# H-bridge.net
KiCad netlist of a schematic drawn in EAGLE
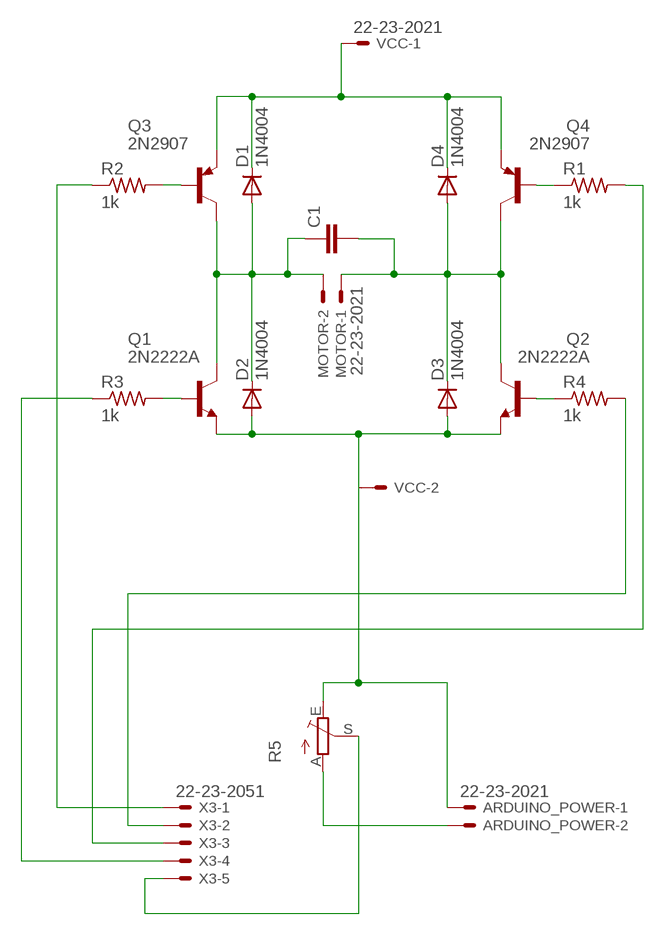
[diagram p0: schematic, sheet 1]

(export (version "E")
  (design (tool "Eeschema 10.0.6"))
  (components
    (comp (ref "ARDUINO_POWER")
      (value "22-23-2021")
      (footprint "eagle-import:22-23-2021")
      (fields (field (name "MF") "MOLEX"))
      (libsource (lib "eagle-import") (part "22-23-2021"))
    )
    (comp (ref "C1")
      (value "C2.5/2")
      (footprint "eagle-import:C2.5-2")
      (libsource (lib "eagle-import") (part "C2.5/2"))
    )
    (comp (ref "D1")
      (value "1N4004")
      (footprint "eagle-import:DO41-10")
      (libsource (lib "eagle-import") (part "1N4004"))
    )
    (comp (ref "D2")
      (value "1N4004")
      (footprint "eagle-import:DO41-10")
      (libsource (lib "eagle-import") (part "1N4004"))
    )
    (comp (ref "D3")
      (value "1N4004")
      (footprint "eagle-import:DO41-10")
      (libsource (lib "eagle-import") (part "1N4004"))
    )
    (comp (ref "D4")
      (value "1N4004")
      (footprint "eagle-import:DO41-10")
      (libsource (lib "eagle-import") (part "1N4004"))
    )
    (comp (ref "MOTOR")
      (value "22-23-2021")
      (footprint "eagle-import:22-23-2021")
      (fields (field (name "MF") "MOLEX"))
      (libsource (lib "eagle-import") (part "22-23-2021"))
    )
    (comp (ref "Q1")
      (value "2N2222A")
      (footprint "eagle-import:TO18")
      (libsource (lib "eagle-import") (part "2N2222A"))
    )
    (comp (ref "Q2")
      (value "2N2222A")
      (footprint "eagle-import:TO18")
      (libsource (lib "eagle-import") (part "2N2222A"))
    )
    (comp (ref "Q3")
      (value "2N2907")
      (footprint "eagle-import:TO18")
      (libsource (lib "eagle-import") (part "2N2907"))
    )
    (comp (ref "Q4")
      (value "2N2907")
      (footprint "eagle-import:TO18")
      (libsource (lib "eagle-import") (part "2N2907"))
    )
    (comp (ref "R1")
      (value "1k")
      (footprint "eagle-import:0309_12")
      (libsource (lib "eagle-import") (part "R-US_0309/12"))
    )
    (comp (ref "R2")
      (value "1k")
      (footprint "eagle-import:0309_12")
      (libsource (lib "eagle-import") (part "R-US_0309/12"))
    )
    (comp (ref "R3")
      (value "1k")
      (footprint "eagle-import:0309_12")
      (libsource (lib "eagle-import") (part "R-US_0309/12"))
    )
    (comp (ref "R4")
      (value "1k")
      (footprint "eagle-import:0309_12")
      (libsource (lib "eagle-import") (part "R-US_0309/12"))
    )
    (comp (ref "R5")
      (value "TRIM_EU-CA6V")
      (footprint "eagle-import:CA6V")
      (libsource (lib "eagle-import") (part "TRIM_EU-CA6V"))
    )
    (comp (ref "VCC")
      (value "22-23-2021")
      (footprint "eagle-import:22-23-2021")
      (fields (field (name "MF") "MOLEX"))
      (libsource (lib "eagle-import") (part "22-23-2021"))
    )
    (comp (ref "X3")
      (value "22-23-2051")
      (footprint "eagle-import:22-23-2051")
      (fields (field (name "MF") "MOLEX"))
      (libsource (lib "eagle-import") (part "22-23-2051"))
    )
  )
  (nets
    (net (code "1") (name "Net-(ARDUINO_POWERA-S)") (class "Default")
      (node (ref "ARDUINO_POWER") (pin "1") (pinfunction "S_1") (pintype "passive"))
      (node (ref "D2") (pin "A") (pinfunction "A_A") (pintype "passive"))
      (node (ref "D3") (pin "A") (pinfunction "A_A") (pintype "passive"))
      (node (ref "Q1") (pin "1") (pinfunction "E_1") (pintype "passive"))
      (node (ref "Q2") (pin "1") (pinfunction "E_1") (pintype "passive"))
      (node (ref "R5") (pin "E") (pinfunction "E_E") (pintype "passive"))
      (node (ref "VCC") (pin "2") (pinfunction "S_2") (pintype "passive"))
    )
    (net (code "2") (name "Net-(ARDUINO_POWERB-S)") (class "Default")
      (node (ref "ARDUINO_POWER") (pin "2") (pinfunction "S_2") (pintype "passive"))
      (node (ref "R5") (pin "A") (pinfunction "A_A") (pintype "passive"))
    )
    (net (code "3") (name "Net-(MOTORA-S)") (class "Default")
      (node (ref "C1") (pin "2") (pinfunction "2_2") (pintype "passive"))
      (node (ref "D3") (pin "C") (pinfunction "C_C") (pintype "passive"))
      (node (ref "D4") (pin "A") (pinfunction "A_A") (pintype "passive"))
      (node (ref "MOTOR") (pin "1") (pinfunction "S_1") (pintype "passive"))
      (node (ref "Q2") (pin "3") (pinfunction "C_3") (pintype "passive"))
      (node (ref "Q4") (pin "3") (pinfunction "C_3") (pintype "passive"))
    )
    (net (code "4") (name "Net-(MOTORB-S)") (class "Default")
      (node (ref "C1") (pin "1") (pinfunction "1_1") (pintype "passive"))
      (node (ref "D1") (pin "A") (pinfunction "A_A") (pintype "passive"))
      (node (ref "D2") (pin "C") (pinfunction "C_C") (pintype "passive"))
      (node (ref "MOTOR") (pin "2") (pinfunction "S_2") (pintype "passive"))
      (node (ref "Q1") (pin "3") (pinfunction "C_3") (pintype "passive"))
      (node (ref "Q3") (pin "3") (pinfunction "C_3") (pintype "passive"))
    )
    (net (code "5") (name "Net-(Q1-B)") (class "Default")
      (node (ref "Q1") (pin "2") (pinfunction "B_2") (pintype "passive"))
      (node (ref "R3") (pin "2") (pinfunction "2_2") (pintype "passive"))
    )
    (net (code "6") (name "Net-(Q2-B)") (class "Default")
      (node (ref "Q2") (pin "2") (pinfunction "B_2") (pintype "passive"))
      (node (ref "R4") (pin "1") (pinfunction "1_1") (pintype "passive"))
    )
    (net (code "7") (name "Net-(Q3-B)") (class "Default")
      (node (ref "Q3") (pin "2") (pinfunction "B_2") (pintype "passive"))
      (node (ref "R2") (pin "2") (pinfunction "2_2") (pintype "passive"))
    )
    (net (code "8") (name "Net-(Q3-E)") (class "Default")
      (node (ref "D1") (pin "C") (pinfunction "C_C") (pintype "passive"))
      (node (ref "D4") (pin "C") (pinfunction "C_C") (pintype "passive"))
      (node (ref "Q3") (pin "1") (pinfunction "E_1") (pintype "passive"))
      (node (ref "Q4") (pin "1") (pinfunction "E_1") (pintype "passive"))
      (node (ref "VCC") (pin "1") (pinfunction "S_1") (pintype "passive"))
    )
    (net (code "9") (name "Net-(Q4-B)") (class "Default")
      (node (ref "Q4") (pin "2") (pinfunction "B_2") (pintype "passive"))
      (node (ref "R1") (pin "1") (pinfunction "1_1") (pintype "passive"))
    )
    (net (code "10") (name "Net-(X3A-S)") (class "Default")
      (node (ref "R2") (pin "1") (pinfunction "1_1") (pintype "passive"))
      (node (ref "X3") (pin "1") (pinfunction "S_1") (pintype "passive"))
    )
    (net (code "11") (name "Net-(X3B-S)") (class "Default")
      (node (ref "R4") (pin "2") (pinfunction "2_2") (pintype "passive"))
      (node (ref "X3") (pin "2") (pinfunction "S_2") (pintype "passive"))
    )
    (net (code "12") (name "Net-(X3C-S)") (class "Default")
      (node (ref "R1") (pin "2") (pinfunction "2_2") (pintype "passive"))
      (node (ref "X3") (pin "3") (pinfunction "S_3") (pintype "passive"))
    )
    (net (code "13") (name "Net-(X3D-S)") (class "Default")
      (node (ref "R3") (pin "1") (pinfunction "1_1") (pintype "passive"))
      (node (ref "X3") (pin "4") (pinfunction "S_4") (pintype "passive"))
    )
    (net (code "14") (name "Net-(X3E-S)") (class "Default")
      (node (ref "R5") (pin "S") (pinfunction "S_S") (pintype "passive"))
      (node (ref "X3") (pin "5") (pinfunction "S_5") (pintype "passive"))
    )
  )
)
